# FRONT_DDR.net
KiCad netlist of a schematic drawn in Altium Designer
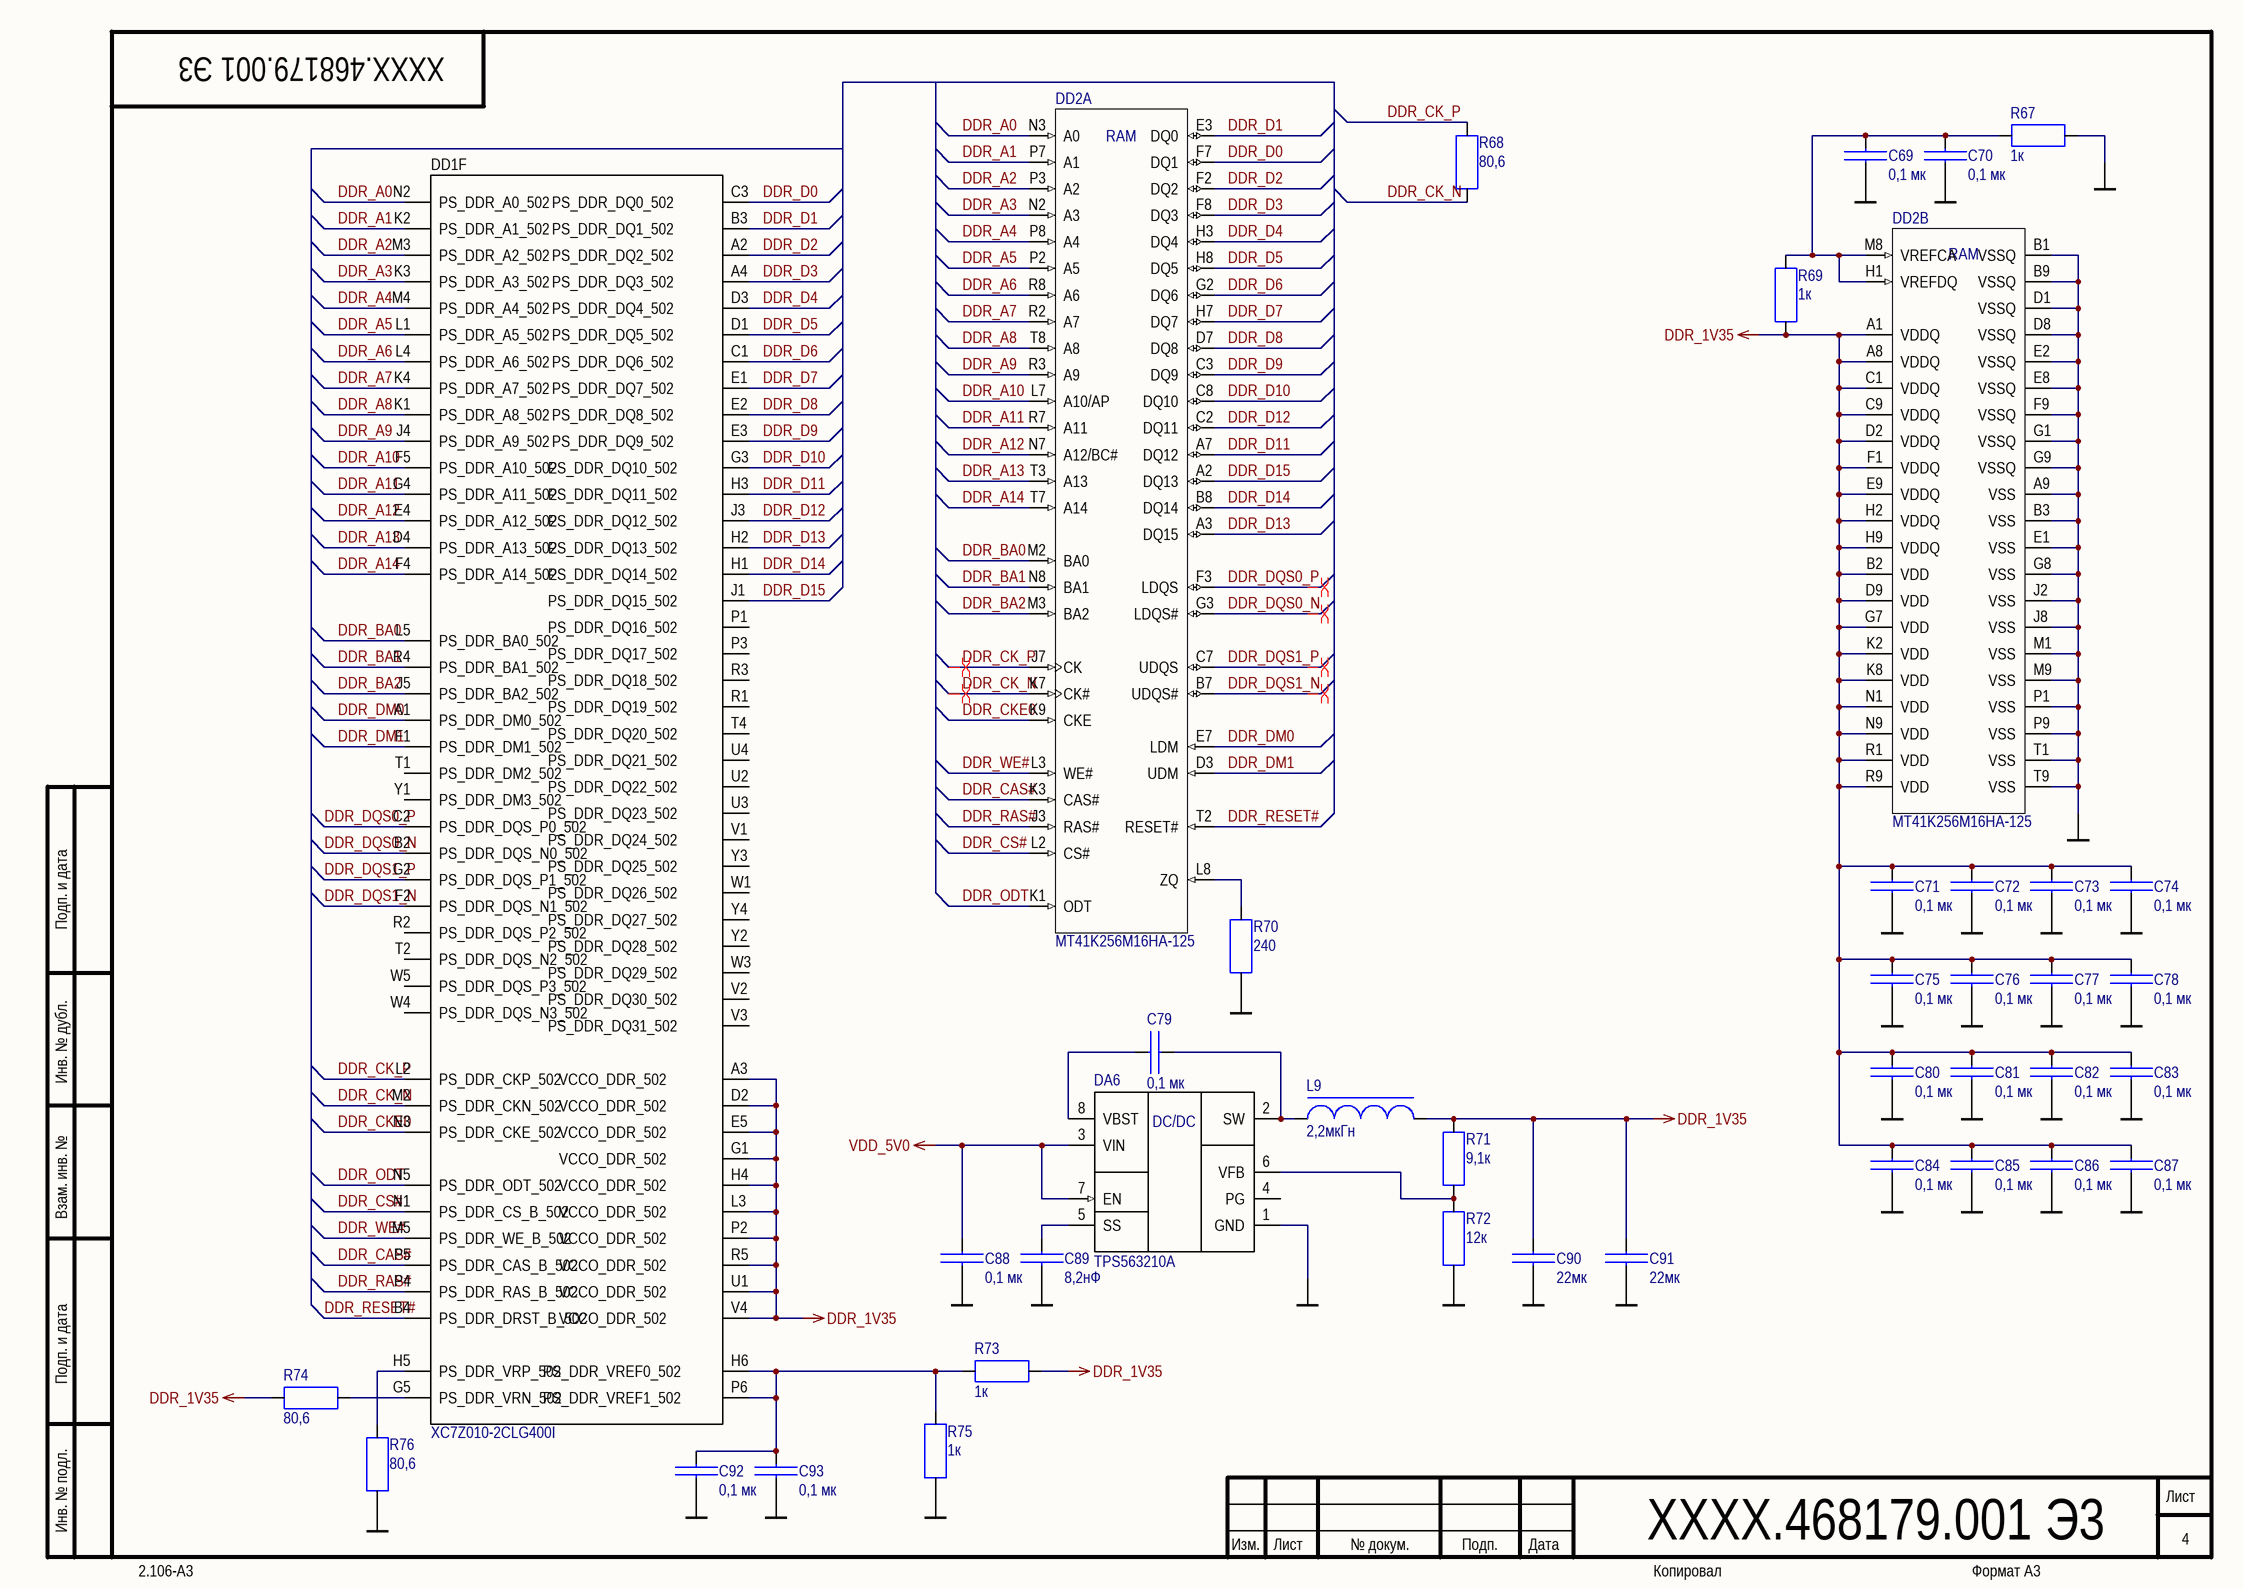
[diagram p0: FRONT_DDR.SchDoc]

(export (version "E")
  (design (tool "Eeschema 10.0.6"))
  (components
    (comp (ref "C69")
      (value "CC0402KRX5R6BB104")
      (footprint "CAPC1005X05L")
      (description "ЧИП конденсатор")
      (fields
        (field (name "NOMINAL") "0,1 мк")
        (field (name "MANUFACTURER") "Yageo")
        (field (name "TOLERANCE") "10%")
      )
      (libsource (lib "Database_Gost") (part "Capacitor const"))
    )
    (comp (ref "C70")
      (value "CC0402KRX5R6BB104")
      (footprint "CAPC1005X05L")
      (description "ЧИП конденсатор")
      (fields
        (field (name "NOMINAL") "0,1 мк")
        (field (name "MANUFACTURER") "Yageo")
        (field (name "TOLERANCE") "10%")
      )
      (libsource (lib "Database_Gost") (part "Capacitor const"))
    )
    (comp (ref "C71")
      (value "CC0402KRX5R6BB104")
      (footprint "CAPC1005X05L")
      (description "ЧИП конденсатор")
      (fields
        (field (name "NOMINAL") "0,1 мк")
        (field (name "MANUFACTURER") "Yageo")
        (field (name "TOLERANCE") "10%")
      )
      (libsource (lib "Database_Gost") (part "Capacitor const"))
    )
    (comp (ref "C72")
      (value "CC0402KRX5R6BB104")
      (footprint "CAPC1005X05L")
      (description "ЧИП конденсатор")
      (fields
        (field (name "NOMINAL") "0,1 мк")
        (field (name "MANUFACTURER") "Yageo")
        (field (name "TOLERANCE") "10%")
      )
      (libsource (lib "Database_Gost") (part "Capacitor const"))
    )
    (comp (ref "C73")
      (value "CC0402KRX5R6BB104")
      (footprint "CAPC1005X05L")
      (description "ЧИП конденсатор")
      (fields
        (field (name "NOMINAL") "0,1 мк")
        (field (name "MANUFACTURER") "Yageo")
        (field (name "TOLERANCE") "10%")
      )
      (libsource (lib "Database_Gost") (part "Capacitor const"))
    )
    (comp (ref "C74")
      (value "CC0402KRX5R6BB104")
      (footprint "CAPC1005X05L")
      (description "ЧИП конденсатор")
      (fields
        (field (name "NOMINAL") "0,1 мк")
        (field (name "MANUFACTURER") "Yageo")
        (field (name "TOLERANCE") "10%")
      )
      (libsource (lib "Database_Gost") (part "Capacitor const"))
    )
    (comp (ref "C75")
      (value "CC0402KRX5R6BB104")
      (footprint "CAPC1005X05L")
      (description "ЧИП конденсатор")
      (fields
        (field (name "NOMINAL") "0,1 мк")
        (field (name "MANUFACTURER") "Yageo")
        (field (name "TOLERANCE") "10%")
      )
      (libsource (lib "Database_Gost") (part "Capacitor const"))
    )
    (comp (ref "C76")
      (value "CC0402KRX5R6BB104")
      (footprint "CAPC1005X05L")
      (description "ЧИП конденсатор")
      (fields
        (field (name "NOMINAL") "0,1 мк")
        (field (name "MANUFACTURER") "Yageo")
        (field (name "TOLERANCE") "10%")
      )
      (libsource (lib "Database_Gost") (part "Capacitor const"))
    )
    (comp (ref "C77")
      (value "CC0402KRX5R6BB104")
      (footprint "CAPC1005X05L")
      (description "ЧИП конденсатор")
      (fields
        (field (name "NOMINAL") "0,1 мк")
        (field (name "MANUFACTURER") "Yageo")
        (field (name "TOLERANCE") "10%")
      )
      (libsource (lib "Database_Gost") (part "Capacitor const"))
    )
    (comp (ref "C78")
      (value "CC0402KRX5R6BB104")
      (footprint "CAPC1005X05L")
      (description "ЧИП конденсатор")
      (fields
        (field (name "NOMINAL") "0,1 мк")
        (field (name "MANUFACTURER") "Yageo")
        (field (name "TOLERANCE") "10%")
      )
      (libsource (lib "Database_Gost") (part "Capacitor const"))
    )
    (comp (ref "C79")
      (value "CC0402KRX5R6BB104")
      (footprint "CAPC1005X05L")
      (description "ЧИП конденсатор")
      (fields
        (field (name "NOMINAL") "0,1 мк")
        (field (name "MANUFACTURER") "Yageo")
        (field (name "TOLERANCE") "10%")
      )
      (libsource (lib "Database_Gost") (part "Capacitor const"))
    )
    (comp (ref "C80")
      (value "CC0402KRX5R6BB104")
      (footprint "CAPC1005X05L")
      (description "ЧИП конденсатор")
      (fields
        (field (name "NOMINAL") "0,1 мк")
        (field (name "MANUFACTURER") "Yageo")
        (field (name "TOLERANCE") "10%")
      )
      (libsource (lib "Database_Gost") (part "Capacitor const"))
    )
    (comp (ref "C81")
      (value "CC0402KRX5R6BB104")
      (footprint "CAPC1005X05L")
      (description "ЧИП конденсатор")
      (fields
        (field (name "NOMINAL") "0,1 мк")
        (field (name "MANUFACTURER") "Yageo")
        (field (name "TOLERANCE") "10%")
      )
      (libsource (lib "Database_Gost") (part "Capacitor const"))
    )
    (comp (ref "C82")
      (value "CC0402KRX5R6BB104")
      (footprint "CAPC1005X05L")
      (description "ЧИП конденсатор")
      (fields
        (field (name "NOMINAL") "0,1 мк")
        (field (name "MANUFACTURER") "Yageo")
        (field (name "TOLERANCE") "10%")
      )
      (libsource (lib "Database_Gost") (part "Capacitor const"))
    )
    (comp (ref "C83")
      (value "CC0402KRX5R6BB104")
      (footprint "CAPC1005X05L")
      (description "ЧИП конденсатор")
      (fields
        (field (name "NOMINAL") "0,1 мк")
        (field (name "MANUFACTURER") "Yageo")
        (field (name "TOLERANCE") "10%")
      )
      (libsource (lib "Database_Gost") (part "Capacitor const"))
    )
    (comp (ref "C84")
      (value "CC0402KRX5R6BB104")
      (footprint "CAPC1005X05L")
      (description "ЧИП конденсатор")
      (fields
        (field (name "NOMINAL") "0,1 мк")
        (field (name "MANUFACTURER") "Yageo")
        (field (name "TOLERANCE") "10%")
      )
      (libsource (lib "Database_Gost") (part "Capacitor const"))
    )
    (comp (ref "C85")
      (value "CC0402KRX5R6BB104")
      (footprint "CAPC1005X05L")
      (description "ЧИП конденсатор")
      (fields
        (field (name "NOMINAL") "0,1 мк")
        (field (name "MANUFACTURER") "Yageo")
        (field (name "TOLERANCE") "10%")
      )
      (libsource (lib "Database_Gost") (part "Capacitor const"))
    )
    (comp (ref "C86")
      (value "CC0402KRX5R6BB104")
      (footprint "CAPC1005X05L")
      (description "ЧИП конденсатор")
      (fields
        (field (name "NOMINAL") "0,1 мк")
        (field (name "MANUFACTURER") "Yageo")
        (field (name "TOLERANCE") "10%")
      )
      (libsource (lib "Database_Gost") (part "Capacitor const"))
    )
    (comp (ref "C87")
      (value "CC0402KRX5R6BB104")
      (footprint "CAPC1005X05L")
      (description "ЧИП конденсатор")
      (fields
        (field (name "NOMINAL") "0,1 мк")
        (field (name "MANUFACTURER") "Yageo")
        (field (name "TOLERANCE") "10%")
      )
      (libsource (lib "Database_Gost") (part "Capacitor const"))
    )
    (comp (ref "C88")
      (value "CC0402KRX5R6BB104")
      (footprint "CAPC1005X05L")
      (description "ЧИП конденсатор")
      (fields
        (field (name "NOMINAL") "0,1 мк")
        (field (name "MANUFACTURER") "Yageo")
        (field (name "TOLERANCE") "10%")
      )
      (libsource (lib "Database_Gost") (part "Capacitor const"))
    )
    (comp (ref "C89")
      (value "CC0402KRX7R9BB822")
      (footprint "CAPC1005X05L")
      (description "ЧИП конденсатор")
      (fields
        (field (name "NOMINAL") "8,2нФ")
        (field (name "MANUFACTURER") "Yageo")
        (field (name "TOLERANCE") "10%")
      )
      (libsource (lib "Database_Gost") (part "Capacitor const"))
    )
    (comp (ref "C90")
      (value "CC0805MKX5R5BB226")
      (footprint "CAPC2012X09L")
      (description "ЧИП конденсатор")
      (fields
        (field (name "NOMINAL") "22мк")
        (field (name "MANUFACTURER") "Yageo")
        (field (name "TOLERANCE") "0,2")
      )
      (libsource (lib "Database_Gost") (part "Capacitor const"))
    )
    (comp (ref "C91")
      (value "CC0805MKX5R5BB226")
      (footprint "CAPC2012X09L")
      (description "ЧИП конденсатор")
      (fields
        (field (name "NOMINAL") "22мк")
        (field (name "MANUFACTURER") "Yageo")
        (field (name "TOLERANCE") "0,2")
      )
      (libsource (lib "Database_Gost") (part "Capacitor const"))
    )
    (comp (ref "C92")
      (value "CC0402KRX5R6BB104")
      (footprint "CAPC1005X05L")
      (description "ЧИП конденсатор")
      (fields
        (field (name "NOMINAL") "0,1 мк")
        (field (name "MANUFACTURER") "Yageo")
        (field (name "TOLERANCE") "10%")
      )
      (libsource (lib "Database_Gost") (part "Capacitor const"))
    )
    (comp (ref "C93")
      (value "CC0402KRX5R6BB104")
      (footprint "CAPC1005X05L")
      (description "ЧИП конденсатор")
      (fields
        (field (name "NOMINAL") "0,1 мк")
        (field (name "MANUFACTURER") "Yageo")
        (field (name "TOLERANCE") "10%")
      )
      (libsource (lib "Database_Gost") (part "Capacitor const"))
    )
    (comp (ref "DA6")
      (value "TPS563210A")
      (footprint "TSOP65P280X110-8L")
      (description "TPS56x210A, 4.5-V to 17-V Input, 2-A, 3-A Synchrono")
      (fields (field (name "MANUFACTURER") "TI"))
      (libsource (lib "Chips_single") (part "TPS563210A"))
    )
    (comp (ref "DD1")
      (value "XC7Z010-2CLG400I")
      (footprint "BGA400C80P20X20_1700X1700X147")
      (description "Zynq®-7000 SoC Family")
      (fields (field (name "MANUFACTURER") "Xilinx"))
      (libsource (lib "Chips_single") (part "XC7Z010-2CLG400I"))
    )
    (comp (ref "DD2")
      (value "MT41K256M16HA-125")
      (footprint "BGA96C80P9X16_800X1400X110")
      (description "4Gb, x16, 1.35V DDR3L")
      (fields (field (name "MANUFACTURER") "Micron"))
      (libsource (lib "Chips_single") (part "MT41K256M16HA-125"))
    )
    (comp (ref "L9")
      (value "XGL4020-222ME")
      (footprint "INDCXGL4020")
      (description "Shielded Power Inductors")
      (fields (field (name "NOMINAL") "2,2мкГн") (field (name "MANUFACTURER") "Coilcraft"))
      (libsource (lib "Database_Gost") (part "Inductor ferr"))
    )
    (comp (ref "R67")
      (value "RC0402JR-071KL")
      (footprint "RESC1005X04L")
      (description "ЧИП резистор")
      (fields
        (field (name "NOMINAL") "1к")
        (field (name "MANUFACTURER") "Yageo")
        (field (name "TOLERANCE") "5%")
      )
      (libsource (lib "Database_Gost") (part "Resistor const"))
    )
    (comp (ref "R68")
      (value "RC0402FR-0780R6L")
      (footprint "RESC1005X04L")
      (description "ЧИП резистор")
      (fields
        (field (name "NOMINAL") "80,6")
        (field (name "MANUFACTURER") "Yageo")
        (field (name "TOLERANCE") "1%")
      )
      (libsource (lib "Database_Gost") (part "Resistor const"))
    )
    (comp (ref "R69")
      (value "RC0402JR-071KL")
      (footprint "RESC1005X04L")
      (description "ЧИП резистор")
      (fields
        (field (name "NOMINAL") "1к")
        (field (name "MANUFACTURER") "Yageo")
        (field (name "TOLERANCE") "5%")
      )
      (libsource (lib "Database_Gost") (part "Resistor const"))
    )
    (comp (ref "R70")
      (value "RC0402JR-07240RL")
      (footprint "RESC1005X04L")
      (description "ЧИП резистор")
      (fields
        (field (name "NOMINAL") "240")
        (field (name "MANUFACTURER") "Yageo")
        (field (name "TOLERANCE") "5%")
      )
      (libsource (lib "Database_Gost") (part "Resistor const"))
    )
    (comp (ref "R71")
      (value "RC0402JR-079K1L")
      (footprint "RESC1005X04L")
      (description "ЧИП резистор")
      (fields
        (field (name "NOMINAL") "9,1к")
        (field (name "MANUFACTURER") "Yageo")
        (field (name "TOLERANCE") "5%")
      )
      (libsource (lib "Database_Gost") (part "Resistor const"))
    )
    (comp (ref "R72")
      (value "RC0402JR-0712KL")
      (footprint "RESC1005X04L")
      (description "ЧИП резистор")
      (fields
        (field (name "NOMINAL") "12к")
        (field (name "MANUFACTURER") "Yageo")
        (field (name "TOLERANCE") "5%")
      )
      (libsource (lib "Database_Gost") (part "Resistor const"))
    )
    (comp (ref "R73")
      (value "RC0402JR-071KL")
      (footprint "RESC1005X04L")
      (description "ЧИП резистор")
      (fields
        (field (name "NOMINAL") "1к")
        (field (name "MANUFACTURER") "Yageo")
        (field (name "TOLERANCE") "5%")
      )
      (libsource (lib "Database_Gost") (part "Resistor const"))
    )
    (comp (ref "R74")
      (value "RC0402FR-0780R6L")
      (footprint "RESC1005X04L")
      (description "ЧИП резистор")
      (fields
        (field (name "NOMINAL") "80,6")
        (field (name "MANUFACTURER") "Yageo")
        (field (name "TOLERANCE") "1%")
      )
      (libsource (lib "Database_Gost") (part "Resistor const"))
    )
    (comp (ref "R75")
      (value "RC0402JR-071KL")
      (footprint "RESC1005X04L")
      (description "ЧИП резистор")
      (fields
        (field (name "NOMINAL") "1к")
        (field (name "MANUFACTURER") "Yageo")
        (field (name "TOLERANCE") "5%")
      )
      (libsource (lib "Database_Gost") (part "Resistor const"))
    )
    (comp (ref "R76")
      (value "RC0402FR-0780R6L")
      (footprint "RESC1005X04L")
      (description "ЧИП резистор")
      (fields
        (field (name "NOMINAL") "80,6")
        (field (name "MANUFACTURER") "Yageo")
        (field (name "TOLERANCE") "1%")
      )
      (libsource (lib "Database_Gost") (part "Resistor const"))
    )
  )
  (nets
    (net (code "1") (name "/DDR_A0") (class "Default")
      (node (ref "DD1") (pin "N2") (pinfunction "PS_DDR_A0_502_N2") (pintype "passive"))
      (node (ref "DD2") (pin "N3") (pinfunction "A0_N3") (pintype "input"))
    )
    (net (code "2") (name "/DDR_A1") (class "Default")
      (node (ref "DD1") (pin "K2") (pinfunction "PS_DDR_A1_502_K2") (pintype "passive"))
      (node (ref "DD2") (pin "P7") (pinfunction "A1_P7") (pintype "input"))
    )
    (net (code "3") (name "/DDR_A2") (class "Default")
      (node (ref "DD1") (pin "M3") (pinfunction "PS_DDR_A2_502_M3") (pintype "passive"))
      (node (ref "DD2") (pin "P3") (pinfunction "A2_P3") (pintype "input"))
    )
    (net (code "4") (name "/DDR_A3") (class "Default")
      (node (ref "DD1") (pin "K3") (pinfunction "PS_DDR_A3_502_K3") (pintype "passive"))
      (node (ref "DD2") (pin "N2") (pinfunction "A3_N2") (pintype "input"))
    )
    (net (code "5") (name "/DDR_A4") (class "Default")
      (node (ref "DD1") (pin "M4") (pinfunction "PS_DDR_A4_502_M4") (pintype "passive"))
      (node (ref "DD2") (pin "P8") (pinfunction "A4_P8") (pintype "input"))
    )
    (net (code "6") (name "/DDR_A5") (class "Default")
      (node (ref "DD1") (pin "L1") (pinfunction "PS_DDR_A5_502_L1") (pintype "passive"))
      (node (ref "DD2") (pin "P2") (pinfunction "A5_P2") (pintype "input"))
    )
    (net (code "7") (name "/DDR_A6") (class "Default")
      (node (ref "DD1") (pin "L4") (pinfunction "PS_DDR_A6_502_L4") (pintype "passive"))
      (node (ref "DD2") (pin "R8") (pinfunction "A6_R8") (pintype "input"))
    )
    (net (code "8") (name "/DDR_A7") (class "Default")
      (node (ref "DD1") (pin "K4") (pinfunction "PS_DDR_A7_502_K4") (pintype "passive"))
      (node (ref "DD2") (pin "R2") (pinfunction "A7_R2") (pintype "input"))
    )
    (net (code "9") (name "/DDR_A8") (class "Default")
      (node (ref "DD1") (pin "K1") (pinfunction "PS_DDR_A8_502_K1") (pintype "passive"))
      (node (ref "DD2") (pin "T8") (pinfunction "A8_T8") (pintype "input"))
    )
    (net (code "10") (name "/DDR_A9") (class "Default")
      (node (ref "DD1") (pin "J4") (pinfunction "PS_DDR_A9_502_J4") (pintype "passive"))
      (node (ref "DD2") (pin "R3") (pinfunction "A9_R3") (pintype "input"))
    )
    (net (code "11") (name "/DDR_A10") (class "Default")
      (node (ref "DD1") (pin "F5") (pinfunction "PS_DDR_A10_502_F5") (pintype "passive"))
      (node (ref "DD2") (pin "L7") (pinfunction "A10/AP_L7") (pintype "input"))
    )
    (net (code "12") (name "/DDR_A11") (class "Default")
      (node (ref "DD1") (pin "G4") (pinfunction "PS_DDR_A11_502_G4") (pintype "passive"))
      (node (ref "DD2") (pin "R7") (pinfunction "A11_R7") (pintype "input"))
    )
    (net (code "13") (name "/DDR_A12") (class "Default")
      (node (ref "DD1") (pin "E4") (pinfunction "PS_DDR_A12_502_E4") (pintype "passive"))
      (node (ref "DD2") (pin "N7") (pinfunction "A12/BC#_N7") (pintype "input"))
    )
    (net (code "14") (name "/DDR_A13") (class "Default")
      (node (ref "DD1") (pin "D4") (pinfunction "PS_DDR_A13_502_D4") (pintype "passive"))
      (node (ref "DD2") (pin "T3") (pinfunction "A13_T3") (pintype "input"))
    )
    (net (code "15") (name "/DDR_A14") (class "Default")
      (node (ref "DD1") (pin "F4") (pinfunction "PS_DDR_A14_502_F4") (pintype "passive"))
      (node (ref "DD2") (pin "T7") (pinfunction "A14_T7") (pintype "input"))
    )
    (net (code "16") (name "/DDR_BA0") (class "Default")
      (node (ref "DD1") (pin "L5") (pinfunction "PS_DDR_BA0_502_L5") (pintype "passive"))
      (node (ref "DD2") (pin "M2") (pinfunction "BA0_M2") (pintype "input"))
    )
    (net (code "17") (name "/DDR_BA1") (class "Default")
      (node (ref "DD1") (pin "R4") (pinfunction "PS_DDR_BA1_502_R4") (pintype "passive"))
      (node (ref "DD2") (pin "N8") (pinfunction "BA1_N8") (pintype "input"))
    )
    (net (code "18") (name "/DDR_BA2") (class "Default")
      (node (ref "DD1") (pin "J5") (pinfunction "PS_DDR_BA2_502_J5") (pintype "passive"))
      (node (ref "DD2") (pin "M3") (pinfunction "BA2_M3") (pintype "input"))
    )
    (net (code "19") (name "/DDR_CAS#") (class "Default")
      (node (ref "DD1") (pin "P5") (pinfunction "PS_DDR_CAS_B_502_P5") (pintype "passive"))
      (node (ref "DD2") (pin "K3") (pinfunction "CAS#_K3") (pintype "input"))
    )
    (net (code "20") (name "/DDR_CKE0") (class "Default")
      (node (ref "DD1") (pin "N3") (pinfunction "PS_DDR_CKE_502_N3") (pintype "passive"))
      (node (ref "DD2") (pin "K9") (pinfunction "CKE_K9") (pintype "input"))
    )
    (net (code "21") (name "/DDR_CK_N") (class "Default")
      (node (ref "DD1") (pin "M2") (pinfunction "PS_DDR_CKN_502_M2") (pintype "passive"))
      (node (ref "DD2") (pin "K7") (pinfunction "CK#_K7") (pintype "input"))
      (node (ref "R68") (pin "1") (pinfunction "1_1") (pintype "passive"))
    )
    (net (code "22") (name "/DDR_CK_P") (class "Default")
      (node (ref "DD1") (pin "L2") (pinfunction "PS_DDR_CKP_502_L2") (pintype "passive"))
      (node (ref "DD2") (pin "J7") (pinfunction "CK_J7") (pintype "input"))
      (node (ref "R68") (pin "2") (pinfunction "2_2") (pintype "passive"))
    )
    (net (code "23") (name "/DDR_CS#") (class "Default")
      (node (ref "DD1") (pin "N1") (pinfunction "PS_DDR_CS_B_502_N1") (pintype "passive"))
      (node (ref "DD2") (pin "L2") (pinfunction "CS#_L2") (pintype "input"))
    )
    (net (code "24") (name "/DDR_D0") (class "Default")
      (node (ref "DD1") (pin "C3") (pinfunction "PS_DDR_DQ0_502_C3") (pintype "passive"))
      (node (ref "DD2") (pin "F7") (pinfunction "DQ1_F7") (pintype "bidirectional"))
    )
    (net (code "25") (name "/DDR_D1") (class "Default")
      (node (ref "DD1") (pin "B3") (pinfunction "PS_DDR_DQ1_502_B3") (pintype "passive"))
      (node (ref "DD2") (pin "E3") (pinfunction "DQ0_E3") (pintype "bidirectional"))
    )
    (net (code "26") (name "/DDR_D2") (class "Default")
      (node (ref "DD1") (pin "A2") (pinfunction "PS_DDR_DQ2_502_A2") (pintype "passive"))
      (node (ref "DD2") (pin "F2") (pinfunction "DQ2_F2") (pintype "bidirectional"))
    )
    (net (code "27") (name "/DDR_D3") (class "Default")
      (node (ref "DD1") (pin "A4") (pinfunction "PS_DDR_DQ3_502_A4") (pintype "passive"))
      (node (ref "DD2") (pin "F8") (pinfunction "DQ3_F8") (pintype "bidirectional"))
    )
    (net (code "28") (name "/DDR_D4") (class "Default")
      (node (ref "DD1") (pin "D3") (pinfunction "PS_DDR_DQ4_502_D3") (pintype "passive"))
      (node (ref "DD2") (pin "H3") (pinfunction "DQ4_H3") (pintype "bidirectional"))
    )
    (net (code "29") (name "/DDR_D5") (class "Default")
      (node (ref "DD1") (pin "D1") (pinfunction "PS_DDR_DQ5_502_D1") (pintype "passive"))
      (node (ref "DD2") (pin "H8") (pinfunction "DQ5_H8") (pintype "bidirectional"))
    )
    (net (code "30") (name "/DDR_D6") (class "Default")
      (node (ref "DD1") (pin "C1") (pinfunction "PS_DDR_DQ6_502_C1") (pintype "passive"))
      (node (ref "DD2") (pin "G2") (pinfunction "DQ6_G2") (pintype "bidirectional"))
    )
    (net (code "31") (name "/DDR_D7") (class "Default")
      (node (ref "DD1") (pin "E1") (pinfunction "PS_DDR_DQ7_502_E1") (pintype "passive"))
      (node (ref "DD2") (pin "H7") (pinfunction "DQ7_H7") (pintype "bidirectional"))
    )
    (net (code "32") (name "/DDR_D8") (class "Default")
      (node (ref "DD1") (pin "E2") (pinfunction "PS_DDR_DQ8_502_E2") (pintype "passive"))
      (node (ref "DD2") (pin "D7") (pinfunction "DQ8_D7") (pintype "bidirectional"))
    )
    (net (code "33") (name "/DDR_D9") (class "Default")
      (node (ref "DD1") (pin "E3") (pinfunction "PS_DDR_DQ9_502_E3") (pintype "passive"))
      (node (ref "DD2") (pin "C3") (pinfunction "DQ9_C3") (pintype "bidirectional"))
    )
    (net (code "34") (name "/DDR_D10") (class "Default")
      (node (ref "DD1") (pin "G3") (pinfunction "PS_DDR_DQ10_502_G3") (pintype "passive"))
      (node (ref "DD2") (pin "C8") (pinfunction "DQ10_C8") (pintype "bidirectional"))
    )
    (net (code "35") (name "/DDR_D11") (class "Default")
      (node (ref "DD1") (pin "H3") (pinfunction "PS_DDR_DQ11_502_H3") (pintype "passive"))
      (node (ref "DD2") (pin "A7") (pinfunction "DQ12_A7") (pintype "bidirectional"))
    )
    (net (code "36") (name "/DDR_D12") (class "Default")
      (node (ref "DD1") (pin "J3") (pinfunction "PS_DDR_DQ12_502_J3") (pintype "passive"))
      (node (ref "DD2") (pin "C2") (pinfunction "DQ11_C2") (pintype "bidirectional"))
    )
    (net (code "37") (name "/DDR_D13") (class "Default")
      (node (ref "DD1") (pin "H2") (pinfunction "PS_DDR_DQ13_502_H2") (pintype "passive"))
      (node (ref "DD2") (pin "A3") (pinfunction "DQ15_A3") (pintype "bidirectional"))
    )
    (net (code "38") (name "/DDR_D14") (class "Default")
      (node (ref "DD1") (pin "H1") (pinfunction "PS_DDR_DQ14_502_H1") (pintype "passive"))
      (node (ref "DD2") (pin "B8") (pinfunction "DQ14_B8") (pintype "bidirectional"))
    )
    (net (code "39") (name "/DDR_D15") (class "Default")
      (node (ref "DD1") (pin "J1") (pinfunction "PS_DDR_DQ15_502_J1") (pintype "passive"))
      (node (ref "DD2") (pin "A2") (pinfunction "DQ13_A2") (pintype "bidirectional"))
    )
    (net (code "40") (name "/DDR_DM0") (class "Default")
      (node (ref "DD1") (pin "A1") (pinfunction "PS_DDR_DM0_502_A1") (pintype "passive"))
      (node (ref "DD2") (pin "E7") (pinfunction "LDM_E7") (pintype "input"))
    )
    (net (code "41") (name "/DDR_DM1") (class "Default")
      (node (ref "DD1") (pin "F1") (pinfunction "PS_DDR_DM1_502_F1") (pintype "passive"))
      (node (ref "DD2") (pin "D3") (pinfunction "UDM_D3") (pintype "input"))
    )
    (net (code "42") (name "/DDR_DQS0_N") (class "Default")
      (node (ref "DD1") (pin "B2") (pinfunction "PS_DDR_DQS_N0_502_B2") (pintype "passive"))
      (node (ref "DD2") (pin "G3") (pinfunction "LDQS#_G3") (pintype "bidirectional"))
    )
    (net (code "43") (name "/DDR_DQS0_P") (class "Default")
      (node (ref "DD1") (pin "C2") (pinfunction "PS_DDR_DQS_P0_502_C2") (pintype "passive"))
      (node (ref "DD2") (pin "F3") (pinfunction "LDQS_F3") (pintype "bidirectional"))
    )
    (net (code "44") (name "/DDR_DQS1_N") (class "Default")
      (node (ref "DD1") (pin "F2") (pinfunction "PS_DDR_DQS_N1_502_F2") (pintype "passive"))
      (node (ref "DD2") (pin "B7") (pinfunction "UDQS#_B7") (pintype "bidirectional"))
    )
    (net (code "45") (name "/DDR_DQS1_P") (class "Default")
      (node (ref "DD1") (pin "G2") (pinfunction "PS_DDR_DQS_P1_502_G2") (pintype "passive"))
      (node (ref "DD2") (pin "C7") (pinfunction "UDQS_C7") (pintype "bidirectional"))
    )
    (net (code "46") (name "/DDR_ODT") (class "Default")
      (node (ref "DD1") (pin "N5") (pinfunction "PS_DDR_ODT_502_N5") (pintype "passive"))
      (node (ref "DD2") (pin "K1") (pinfunction "ODT_K1") (pintype "input"))
    )
    (net (code "47") (name "/DDR_RAS#") (class "Default")
      (node (ref "DD1") (pin "P4") (pinfunction "PS_DDR_RAS_B_502_P4") (pintype "passive"))
      (node (ref "DD2") (pin "J3") (pinfunction "RAS#_J3") (pintype "input"))
    )
    (net (code "48") (name "/DDR_RESET#") (class "Default")
      (node (ref "DD1") (pin "B4") (pinfunction "PS_DDR_DRST_B_502_B4") (pintype "passive"))
      (node (ref "DD2") (pin "T2") (pinfunction "RESET#_T2") (pintype "input"))
    )
    (net (code "49") (name "/DDR_WE#") (class "Default")
      (node (ref "DD1") (pin "M5") (pinfunction "PS_DDR_WE_B_502_M5") (pintype "passive"))
      (node (ref "DD2") (pin "L3") (pinfunction "WE#_L3") (pintype "input"))
    )
    (net (code "50") (name "DDR_1V35") (class "Default")
      (node (ref "C71") (pin "2") (pinfunction "2_2") (pintype "passive"))
      (node (ref "C72") (pin "2") (pinfunction "2_2") (pintype "passive"))
      (node (ref "C73") (pin "2") (pinfunction "2_2") (pintype "passive"))
      (node (ref "C74") (pin "2") (pinfunction "2_2") (pintype "passive"))
      (node (ref "C75") (pin "2") (pinfunction "2_2") (pintype "passive"))
      (node (ref "C76") (pin "2") (pinfunction "2_2") (pintype "passive"))
      (node (ref "C77") (pin "2") (pinfunction "2_2") (pintype "passive"))
      (node (ref "C78") (pin "2") (pinfunction "2_2") (pintype "passive"))
      (node (ref "C80") (pin "2") (pinfunction "2_2") (pintype "passive"))
      (node (ref "C81") (pin "2") (pinfunction "2_2") (pintype "passive"))
      (node (ref "C82") (pin "2") (pinfunction "2_2") (pintype "passive"))
      (node (ref "C83") (pin "2") (pinfunction "2_2") (pintype "passive"))
      (node (ref "C84") (pin "2") (pinfunction "2_2") (pintype "passive"))
      (node (ref "C85") (pin "2") (pinfunction "2_2") (pintype "passive"))
      (node (ref "C86") (pin "2") (pinfunction "2_2") (pintype "passive"))
      (node (ref "C87") (pin "2") (pinfunction "2_2") (pintype "passive"))
      (node (ref "C90") (pin "2") (pinfunction "2_2") (pintype "passive"))
      (node (ref "C91") (pin "2") (pinfunction "2_2") (pintype "passive"))
      (node (ref "DD1") (pin "A3") (pinfunction "VCCO_DDR_502_A3") (pintype "passive"))
      (node (ref "DD1") (pin "D2") (pinfunction "VCCO_DDR_502_D2") (pintype "passive"))
      (node (ref "DD1") (pin "E5") (pinfunction "VCCO_DDR_502_E5") (pintype "passive"))
      (node (ref "DD1") (pin "G1") (pinfunction "VCCO_DDR_502_G1") (pintype "passive"))
      (node (ref "DD1") (pin "H4") (pinfunction "VCCO_DDR_502_H4") (pintype "passive"))
      (node (ref "DD1") (pin "L3") (pinfunction "VCCO_DDR_502_L3") (pintype "passive"))
      (node (ref "DD1") (pin "P2") (pinfunction "VCCO_DDR_502_P2") (pintype "passive"))
      (node (ref "DD1") (pin "R5") (pinfunction "VCCO_DDR_502_R5") (pintype "passive"))
      (node (ref "DD1") (pin "U1") (pinfunction "VCCO_DDR_502_U1") (pintype "passive"))
      (node (ref "DD1") (pin "V4") (pinfunction "VCCO_DDR_502_V4") (pintype "passive"))
      (node (ref "DD2") (pin "A1") (pinfunction "VDDQ_A1") (pintype "power_in"))
      (node (ref "DD2") (pin "A8") (pinfunction "VDDQ_A8") (pintype "power_in"))
      (node (ref "DD2") (pin "B2") (pinfunction "VDD_B2") (pintype "power_in"))
      (node (ref "DD2") (pin "C1") (pinfunction "VDDQ_C1") (pintype "power_in"))
      (node (ref "DD2") (pin "C9") (pinfunction "VDDQ_C9") (pintype "power_in"))
      (node (ref "DD2") (pin "D2") (pinfunction "VDDQ_D2") (pintype "power_in"))
      (node (ref "DD2") (pin "D9") (pinfunction "VDD_D9") (pintype "power_in"))
      (node (ref "DD2") (pin "E9") (pinfunction "VDDQ_E9") (pintype "power_in"))
      (node (ref "DD2") (pin "F1") (pinfunction "VDDQ_F1") (pintype "power_in"))
      (node (ref "DD2") (pin "G7") (pinfunction "VDD_G7") (pintype "power_in"))
      (node (ref "DD2") (pin "H2") (pinfunction "VDDQ_H2") (pintype "power_in"))
      (node (ref "DD2") (pin "H9") (pinfunction "VDDQ_H9") (pintype "power_in"))
      (node (ref "DD2") (pin "K2") (pinfunction "VDD_K2") (pintype "power_in"))
      (node (ref "DD2") (pin "K8") (pinfunction "VDD_K8") (pintype "power_in"))
      (node (ref "DD2") (pin "N1") (pinfunction "VDD_N1") (pintype "power_in"))
      (node (ref "DD2") (pin "N9") (pinfunction "VDD_N9") (pintype "power_in"))
      (node (ref "DD2") (pin "R1") (pinfunction "VDD_R1") (pintype "power_in"))
      (node (ref "DD2") (pin "R9") (pinfunction "VDD_R9") (pintype "power_in"))
      (node (ref "L9") (pin "1") (pinfunction "1_1") (pintype "passive"))
      (node (ref "R69") (pin "2") (pinfunction "2_2") (pintype "passive"))
      (node (ref "R71") (pin "1") (pinfunction "1_1") (pintype "passive"))
      (node (ref "R73") (pin "1") (pinfunction "1_1") (pintype "passive"))
      (node (ref "R74") (pin "2") (pinfunction "2_2") (pintype "passive"))
    )
    (net (code "51") (name "GND") (class "Default")
      (node (ref "C69") (pin "1") (pinfunction "1_1") (pintype "passive"))
      (node (ref "C70") (pin "1") (pinfunction "1_1") (pintype "passive"))
      (node (ref "C71") (pin "1") (pinfunction "1_1") (pintype "passive"))
      (node (ref "C72") (pin "1") (pinfunction "1_1") (pintype "passive"))
      (node (ref "C73") (pin "1") (pinfunction "1_1") (pintype "passive"))
      (node (ref "C74") (pin "1") (pinfunction "1_1") (pintype "passive"))
      (node (ref "C75") (pin "1") (pinfunction "1_1") (pintype "passive"))
      (node (ref "C76") (pin "1") (pinfunction "1_1") (pintype "passive"))
      (node (ref "C77") (pin "1") (pinfunction "1_1") (pintype "passive"))
      (node (ref "C78") (pin "1") (pinfunction "1_1") (pintype "passive"))
      (node (ref "C80") (pin "1") (pinfunction "1_1") (pintype "passive"))
      (node (ref "C81") (pin "1") (pinfunction "1_1") (pintype "passive"))
      (node (ref "C82") (pin "1") (pinfunction "1_1") (pintype "passive"))
      (node (ref "C83") (pin "1") (pinfunction "1_1") (pintype "passive"))
      (node (ref "C84") (pin "1") (pinfunction "1_1") (pintype "passive"))
      (node (ref "C85") (pin "1") (pinfunction "1_1") (pintype "passive"))
      (node (ref "C86") (pin "1") (pinfunction "1_1") (pintype "passive"))
      (node (ref "C87") (pin "1") (pinfunction "1_1") (pintype "passive"))
      (node (ref "C88") (pin "1") (pinfunction "1_1") (pintype "passive"))
      (node (ref "C89") (pin "1") (pinfunction "1_1") (pintype "passive"))
      (node (ref "C90") (pin "1") (pinfunction "1_1") (pintype "passive"))
      (node (ref "C91") (pin "1") (pinfunction "1_1") (pintype "passive"))
      (node (ref "C92") (pin "1") (pinfunction "1_1") (pintype "passive"))
      (node (ref "C93") (pin "1") (pinfunction "1_1") (pintype "passive"))
      (node (ref "DA6") (pin "1") (pinfunction "GND_1") (pintype "passive"))
      (node (ref "DD2") (pin "A9") (pinfunction "VSS_A9") (pintype "power_in"))
      (node (ref "DD2") (pin "B1") (pinfunction "VSSQ_B1") (pintype "power_in"))
      (node (ref "DD2") (pin "B3") (pinfunction "VSS_B3") (pintype "power_in"))
      (node (ref "DD2") (pin "B9") (pinfunction "VSSQ_B9") (pintype "power_in"))
      (node (ref "DD2") (pin "D1") (pinfunction "VSSQ_D1") (pintype "power_in"))
      (node (ref "DD2") (pin "D8") (pinfunction "VSSQ_D8") (pintype "power_in"))
      (node (ref "DD2") (pin "E1") (pinfunction "VSS_E1") (pintype "power_in"))
      (node (ref "DD2") (pin "E2") (pinfunction "VSSQ_E2") (pintype "power_in"))
      (node (ref "DD2") (pin "E8") (pinfunction "VSSQ_E8") (pintype "power_in"))
      (node (ref "DD2") (pin "F9") (pinfunction "VSSQ_F9") (pintype "power_in"))
      (node (ref "DD2") (pin "G1") (pinfunction "VSSQ_G1") (pintype "power_in"))
      (node (ref "DD2") (pin "G8") (pinfunction "VSS_G8") (pintype "power_in"))
      (node (ref "DD2") (pin "G9") (pinfunction "VSSQ_G9") (pintype "power_in"))
      (node (ref "DD2") (pin "J2") (pinfunction "VSS_J2") (pintype "power_in"))
      (node (ref "DD2") (pin "J8") (pinfunction "VSS_J8") (pintype "power_in"))
      (node (ref "DD2") (pin "M1") (pinfunction "VSS_M1") (pintype "power_in"))
      (node (ref "DD2") (pin "M9") (pinfunction "VSS_M9") (pintype "power_in"))
      (node (ref "DD2") (pin "P1") (pinfunction "VSS_P1") (pintype "power_in"))
      (node (ref "DD2") (pin "P9") (pinfunction "VSS_P9") (pintype "power_in"))
      (node (ref "DD2") (pin "T1") (pinfunction "VSS_T1") (pintype "power_in"))
      (node (ref "DD2") (pin "T9") (pinfunction "VSS_T9") (pintype "power_in"))
      (node (ref "R67") (pin "2") (pinfunction "2_2") (pintype "passive"))
      (node (ref "R70") (pin "1") (pinfunction "1_1") (pintype "passive"))
      (node (ref "R72") (pin "2") (pinfunction "2_2") (pintype "passive"))
      (node (ref "R75") (pin "1") (pinfunction "1_1") (pintype "passive"))
      (node (ref "R76") (pin "1") (pinfunction "1_1") (pintype "passive"))
    )
    (net (code "52") (name "Net-(DA6-SS)") (class "Default")
      (node (ref "C89") (pin "2") (pinfunction "2_2") (pintype "passive"))
      (node (ref "DA6") (pin "5") (pinfunction "SS_5") (pintype "passive"))
    )
    (net (code "53") (name "Net-(DA6-SW)") (class "Default")
      (node (ref "C79") (pin "2") (pinfunction "2_2") (pintype "passive"))
      (node (ref "DA6") (pin "2") (pinfunction "SW_2") (pintype "passive"))
      (node (ref "L9") (pin "2") (pinfunction "2_2") (pintype "passive"))
    )
    (net (code "54") (name "Net-(DA6-VBST)") (class "Default")
      (node (ref "C79") (pin "1") (pinfunction "1_1") (pintype "passive"))
      (node (ref "DA6") (pin "8") (pinfunction "VBST_8") (pintype "passive"))
    )
    (net (code "55") (name "Net-(DA6-VFB)") (class "Default")
      (node (ref "DA6") (pin "6") (pinfunction "VFB_6") (pintype "passive"))
      (node (ref "R71") (pin "2") (pinfunction "2_2") (pintype "passive"))
      (node (ref "R72") (pin "1") (pinfunction "1_1") (pintype "passive"))
    )
    (net (code "56") (name "Net-(DD1F-PS_DDR_VREF0_502)") (class "Default")
      (node (ref "C92") (pin "2") (pinfunction "2_2") (pintype "passive"))
      (node (ref "C93") (pin "2") (pinfunction "2_2") (pintype "passive"))
      (node (ref "DD1") (pin "H6") (pinfunction "PS_DDR_VREF0_502_H6") (pintype "passive"))
      (node (ref "DD1") (pin "P6") (pinfunction "PS_DDR_VREF1_502_P6") (pintype "passive"))
      (node (ref "R73") (pin "2") (pinfunction "2_2") (pintype "passive"))
      (node (ref "R75") (pin "2") (pinfunction "2_2") (pintype "passive"))
    )
    (net (code "57") (name "Net-(DD1F-PS_DDR_VRN_502)") (class "Default")
      (node (ref "DD1") (pin "G5") (pinfunction "PS_DDR_VRN_502_G5") (pintype "passive"))
      (node (ref "R74") (pin "1") (pinfunction "1_1") (pintype "passive"))
    )
    (net (code "58") (name "Net-(DD1F-PS_DDR_VRP_502)") (class "Default")
      (node (ref "DD1") (pin "H5") (pinfunction "PS_DDR_VRP_502_H5") (pintype "passive"))
      (node (ref "R76") (pin "2") (pinfunction "2_2") (pintype "passive"))
    )
    (net (code "59") (name "Net-(DD2A-ZQ)") (class "Default")
      (node (ref "DD2") (pin "L8") (pinfunction "ZQ_L8") (pintype "input"))
      (node (ref "R70") (pin "2") (pinfunction "2_2") (pintype "passive"))
    )
    (net (code "60") (name "Net-(DD2B-VREFCA)") (class "Default")
      (node (ref "C69") (pin "2") (pinfunction "2_2") (pintype "passive"))
      (node (ref "C70") (pin "2") (pinfunction "2_2") (pintype "passive"))
      (node (ref "DD2") (pin "H1") (pinfunction "VREFDQ_H1") (pintype "input"))
      (node (ref "DD2") (pin "M8") (pinfunction "VREFCA_M8") (pintype "input"))
      (node (ref "R67") (pin "1") (pinfunction "1_1") (pintype "passive"))
      (node (ref "R69") (pin "1") (pinfunction "1_1") (pintype "passive"))
    )
    (net (code "61") (name "VDD_5V0") (class "Default")
      (node (ref "C88") (pin "2") (pinfunction "2_2") (pintype "passive"))
      (node (ref "DA6") (pin "3") (pinfunction "VIN_3") (pintype "passive"))
      (node (ref "DA6") (pin "7") (pinfunction "EN_7") (pintype "input"))
    )
    (net (code "62") (name "unconnected-(DA6-PG-Pad4)") (class "Default")
      (node (ref "DA6") (pin "4") (pinfunction "PG_4") (pintype "passive"))
    )
    (net (code "63") (name "unconnected-(DD1F-PS_DDR_DM2_502-PadT1)") (class "Default")
      (node (ref "DD1") (pin "T1") (pinfunction "PS_DDR_DM2_502_T1") (pintype "passive"))
    )
    (net (code "64") (name "unconnected-(DD1F-PS_DDR_DM3_502-PadY1)") (class "Default")
      (node (ref "DD1") (pin "Y1") (pinfunction "PS_DDR_DM3_502_Y1") (pintype "passive"))
    )
    (net (code "65") (name "unconnected-(DD1F-PS_DDR_DQ16_502-PadP1)") (class "Default")
      (node (ref "DD1") (pin "P1") (pinfunction "PS_DDR_DQ16_502_P1") (pintype "passive"))
    )
    (net (code "66") (name "unconnected-(DD1F-PS_DDR_DQ17_502-PadP3)") (class "Default")
      (node (ref "DD1") (pin "P3") (pinfunction "PS_DDR_DQ17_502_P3") (pintype "passive"))
    )
    (net (code "67") (name "unconnected-(DD1F-PS_DDR_DQ18_502-PadR3)") (class "Default")
      (node (ref "DD1") (pin "R3") (pinfunction "PS_DDR_DQ18_502_R3") (pintype "passive"))
    )
    (net (code "68") (name "unconnected-(DD1F-PS_DDR_DQ19_502-PadR1)") (class "Default")
      (node (ref "DD1") (pin "R1") (pinfunction "PS_DDR_DQ19_502_R1") (pintype "passive"))
    )
    (net (code "69") (name "unconnected-(DD1F-PS_DDR_DQ20_502-PadT4)") (class "Default")
      (node (ref "DD1") (pin "T4") (pinfunction "PS_DDR_DQ20_502_T4") (pintype "passive"))
    )
    (net (code "70") (name "unconnected-(DD1F-PS_DDR_DQ21_502-PadU4)") (class "Default")
      (node (ref "DD1") (pin "U4") (pinfunction "PS_DDR_DQ21_502_U4") (pintype "passive"))
    )
    (net (code "71") (name "unconnected-(DD1F-PS_DDR_DQ22_502-PadU2)") (class "Default")
      (node (ref "DD1") (pin "U2") (pinfunction "PS_DDR_DQ22_502_U2") (pintype "passive"))
    )
    (net (code "72") (name "unconnected-(DD1F-PS_DDR_DQ23_502-PadU3)") (class "Default")
      (node (ref "DD1") (pin "U3") (pinfunction "PS_DDR_DQ23_502_U3") (pintype "passive"))
    )
    (net (code "73") (name "unconnected-(DD1F-PS_DDR_DQ24_502-PadV1)") (class "Default")
      (node (ref "DD1") (pin "V1") (pinfunction "PS_DDR_DQ24_502_V1") (pintype "passive"))
    )
    (net (code "74") (name "unconnected-(DD1F-PS_DDR_DQ25_502-PadY3)") (class "Default")
      (node (ref "DD1") (pin "Y3") (pinfunction "PS_DDR_DQ25_502_Y3") (pintype "passive"))
    )
    (net (code "75") (name "unconnected-(DD1F-PS_DDR_DQ26_502-PadW1)") (class "Default")
      (node (ref "DD1") (pin "W1") (pinfunction "PS_DDR_DQ26_502_W1") (pintype "passive"))
    )
    (net (code "76") (name "unconnected-(DD1F-PS_DDR_DQ27_502-PadY4)") (class "Default")
      (node (ref "DD1") (pin "Y4") (pinfunction "PS_DDR_DQ27_502_Y4") (pintype "passive"))
    )
    (net (code "77") (name "unconnected-(DD1F-PS_DDR_DQ28_502-PadY2)") (class "Default")
      (node (ref "DD1") (pin "Y2") (pinfunction "PS_DDR_DQ28_502_Y2") (pintype "passive"))
    )
    (net (code "78") (name "unconnected-(DD1F-PS_DDR_DQ29_502-PadW3)") (class "Default")
      (node (ref "DD1") (pin "W3") (pinfunction "PS_DDR_DQ29_502_W3") (pintype "passive"))
    )
    (net (code "79") (name "unconnected-(DD1F-PS_DDR_DQ30_502-PadV2)") (class "Default")
      (node (ref "DD1") (pin "V2") (pinfunction "PS_DDR_DQ30_502_V2") (pintype "passive"))
    )
    (net (code "80") (name "unconnected-(DD1F-PS_DDR_DQ31_502-PadV3)") (class "Default")
      (node (ref "DD1") (pin "V3") (pinfunction "PS_DDR_DQ31_502_V3") (pintype "passive"))
    )
    (net (code "81") (name "unconnected-(DD1F-PS_DDR_DQS_N2_502-PadT2)") (class "Default")
      (node (ref "DD1") (pin "T2") (pinfunction "PS_DDR_DQS_N2_502_T2") (pintype "passive"))
    )
    (net (code "82") (name "unconnected-(DD1F-PS_DDR_DQS_N3_502-PadW4)") (class "Default")
      (node (ref "DD1") (pin "W4") (pinfunction "PS_DDR_DQS_N3_502_W4") (pintype "passive"))
    )
    (net (code "83") (name "unconnected-(DD1F-PS_DDR_DQS_P2_502-PadR2)") (class "Default")
      (node (ref "DD1") (pin "R2") (pinfunction "PS_DDR_DQS_P2_502_R2") (pintype "passive"))
    )
    (net (code "84") (name "unconnected-(DD1F-PS_DDR_DQS_P3_502-PadW5)") (class "Default")
      (node (ref "DD1") (pin "W5") (pinfunction "PS_DDR_DQS_P3_502_W5") (pintype "passive"))
    )
  )
)
